# TiltyDuo.net
KiCad netlist of a schematic drawn in EAGLE
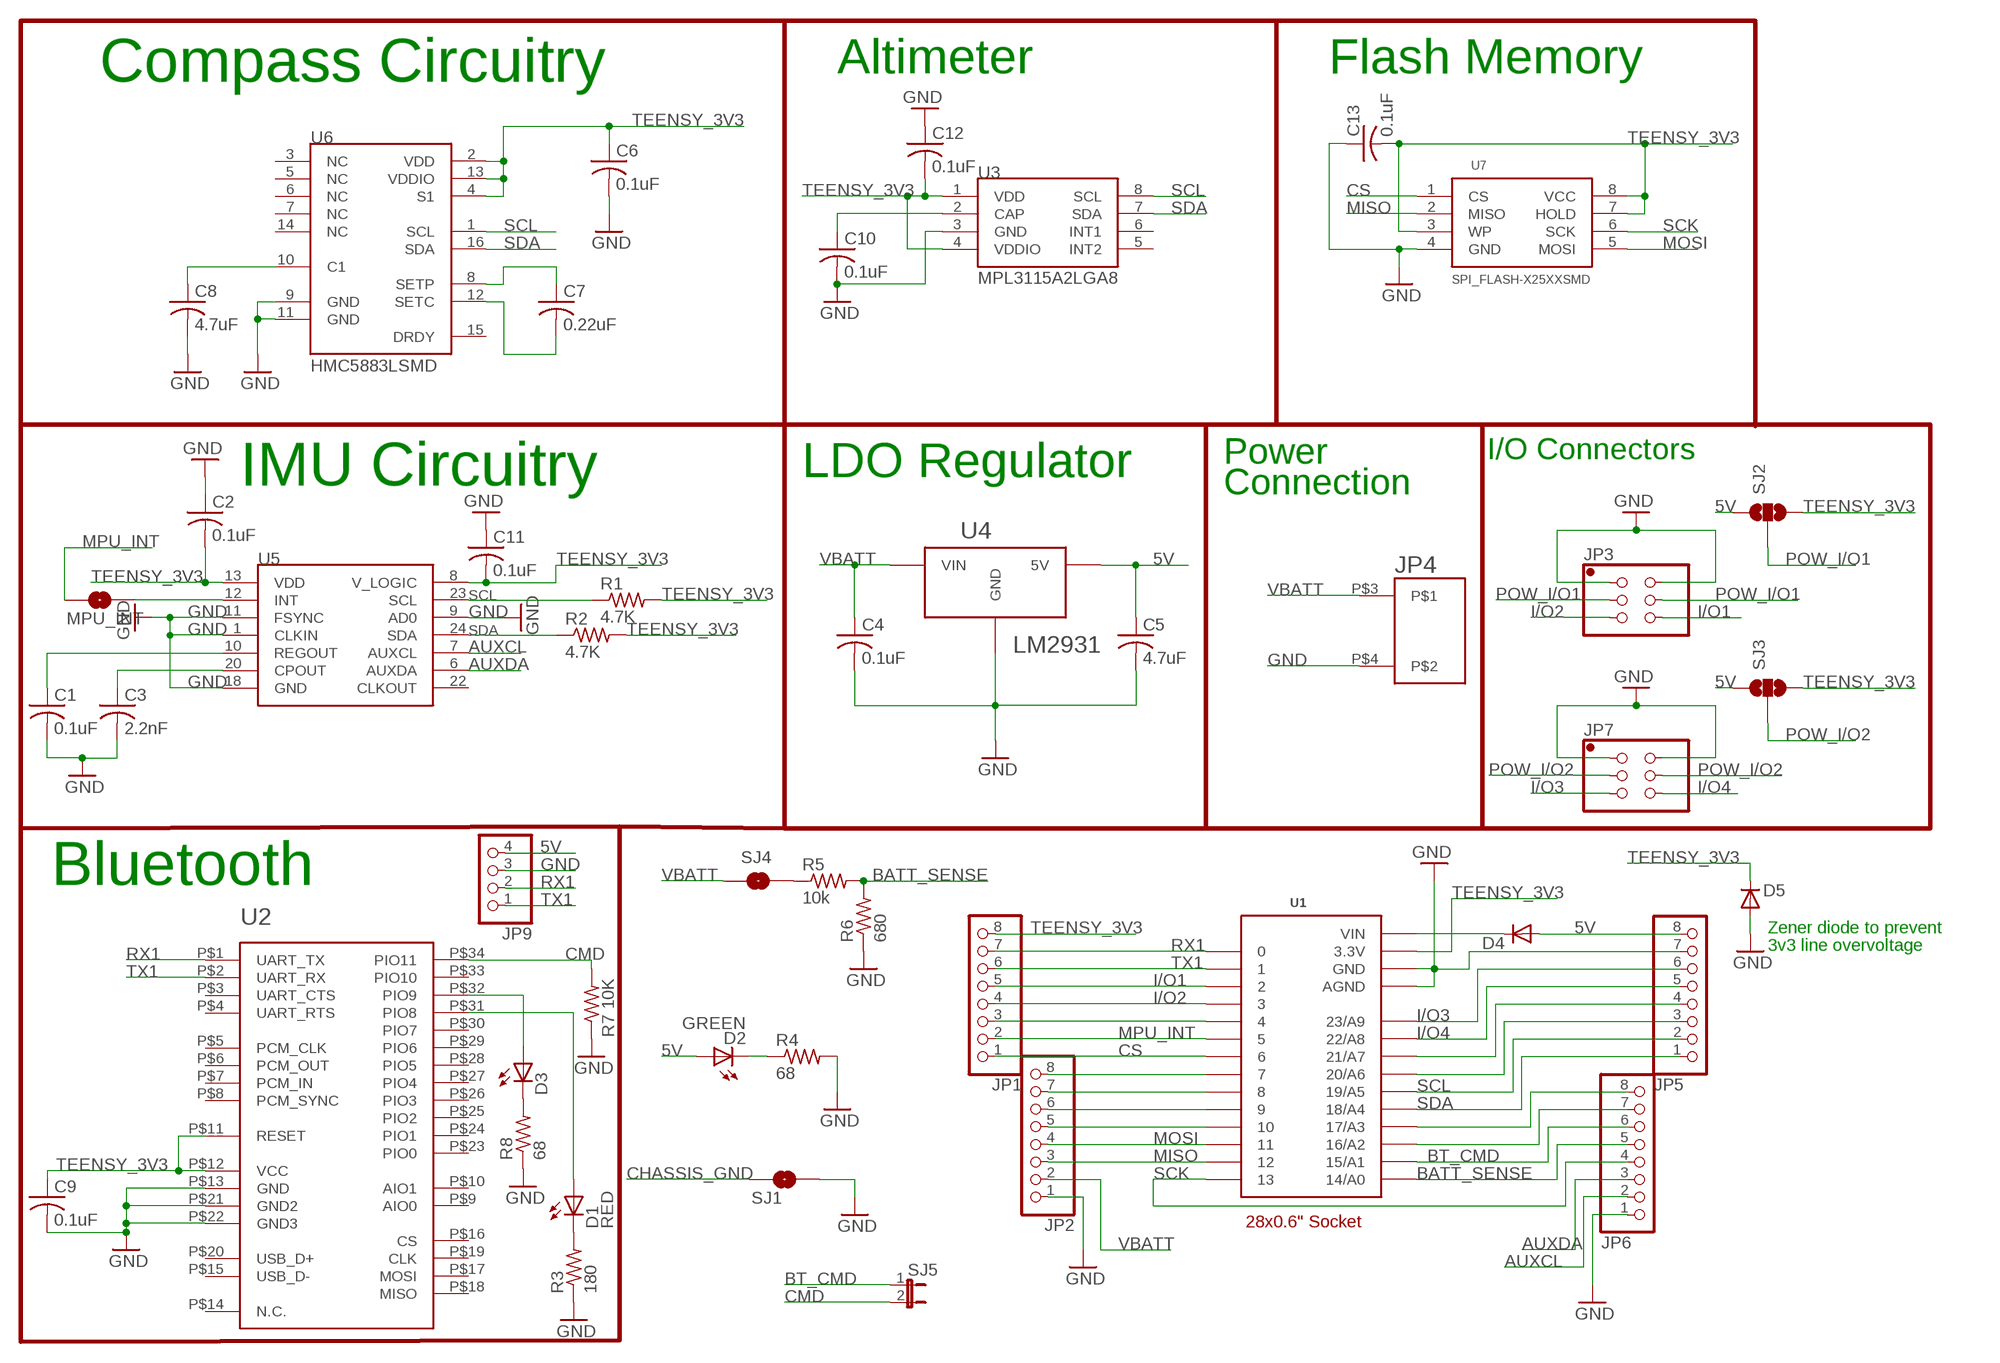
[diagram p0: schematic, sheet 1]

(export (version "E")
  (design (tool "Eeschema 10.0.6"))
  (components
    (comp (ref "C1")
      (value "0.1uF")
      (footprint "eagle-import:C0603")
      (libsource (lib "eagle-import") (part "C-USC0603"))
    )
    (comp (ref "C2")
      (value "0.1uF")
      (footprint "eagle-import:C0603")
      (libsource (lib "eagle-import") (part "C-USC0603"))
    )
    (comp (ref "C3")
      (value "2.2nF")
      (footprint "eagle-import:C0603")
      (libsource (lib "eagle-import") (part "C-USC0603"))
    )
    (comp (ref "C4")
      (value "0.1uF")
      (footprint "eagle-import:C0603")
      (libsource (lib "eagle-import") (part "C-USC0603"))
    )
    (comp (ref "C5")
      (value "4.7uF")
      (footprint "eagle-import:C0603")
      (libsource (lib "eagle-import") (part "C-USC0603"))
    )
    (comp (ref "C6")
      (value "0.1uF")
      (footprint "eagle-import:C0603")
      (libsource (lib "eagle-import") (part "C-USC0603"))
    )
    (comp (ref "C7")
      (value "0.22uF")
      (footprint "eagle-import:C0603")
      (libsource (lib "eagle-import") (part "C-USC0603"))
    )
    (comp (ref "C8")
      (value "4.7uF")
      (footprint "eagle-import:C0603")
      (libsource (lib "eagle-import") (part "C-USC0603"))
    )
    (comp (ref "C9")
      (value "0.1uF")
      (footprint "eagle-import:C0603")
      (libsource (lib "eagle-import") (part "C-USC0603"))
    )
    (comp (ref "C10")
      (value "0.1uF")
      (footprint "eagle-import:C0603")
      (libsource (lib "eagle-import") (part "C-USC0603"))
    )
    (comp (ref "C11")
      (value "0.1uF")
      (footprint "eagle-import:C0603")
      (libsource (lib "eagle-import") (part "C-USC0603"))
    )
    (comp (ref "C12")
      (value "0.1uF")
      (footprint "eagle-import:C0603")
      (libsource (lib "eagle-import") (part "C-USC0603"))
    )
    (comp (ref "C13")
      (value "0.1uF")
      (footprint "eagle-import:C0603")
      (libsource (lib "eagle-import") (part "C-USC0603"))
    )
    (comp (ref "D1")
      (value "RED")
      (footprint "eagle-import:LED-0805")
      (libsource (lib "eagle-import") (part "LED-GREENLED-0805_NO_SILK"))
    )
    (comp (ref "D2")
      (value "GREEN")
      (footprint "eagle-import:LED-0805")
      (libsource (lib "eagle-import") (part "LED-GREENLED-0805_NO_SILK"))
    )
    (comp (ref "D3")
      (value "YELLOW")
      (footprint "eagle-import:LED-0805")
      (libsource (lib "eagle-import") (part "LED-GREENLED-0805_NO_SILK"))
    )
    (comp (ref "D4")
      (value "DIODESOT23")
      (footprint "eagle-import:SOT23-3")
      (fields (field (name "PART#") "BAT54FSTR-ND"))
      (libsource (lib "eagle-import") (part "DIODESOT23"))
    )
    (comp (ref "D5")
      (value "DIODESOT23")
      (footprint "eagle-import:SOT23-3")
      (fields (field (name "PART#") "BZX84C3V3LT1GOSCT-ND"))
      (libsource (lib "eagle-import") (part "DIODESOT23"))
    )
    (comp (ref "JP1")
      (value "PINHD-1X81X08_NO_SILK_LOCK")
      (footprint "eagle-import:1X08_NO_SS_LOCKING")
      (libsource (lib "eagle-import") (part "PINHD-1X81X08_NO_SILK_LOCK"))
    )
    (comp (ref "JP2")
      (value "PINHD-1X81X08_NO_SILK_LOCK")
      (footprint "eagle-import:1X08_NO_SS_LOCKING")
      (libsource (lib "eagle-import") (part "PINHD-1X81X08_NO_SILK_LOCK"))
    )
    (comp (ref "JP3")
      (value "PINHD-2X32X03_NO_SS_LOCK")
      (footprint "eagle-import:2X03_NO_SS_LOCK")
      (libsource (lib "eagle-import") (part "PINHD-2X32X03_NO_SS_LOCK"))
    )
    (comp (ref "JP4")
      (value "2-POS_SMD_TERM_BLOCK")
      (footprint "eagle-import:2-POS_SMD_TERMINAL_BLOCK")
      (fields (field (name "PART#") "277-2337-1-ND"))
      (libsource (lib "eagle-import") (part "2-POS_SMD_TERM_BLOCK"))
    )
    (comp (ref "JP5")
      (value "PINHD-1X81X08_NO_SILK_LOCK")
      (footprint "eagle-import:1X08_NO_SS_LOCKING")
      (libsource (lib "eagle-import") (part "PINHD-1X81X08_NO_SILK_LOCK"))
    )
    (comp (ref "JP6")
      (value "PINHD-1X81X08_NO_SILK_LOCK")
      (footprint "eagle-import:1X08_NO_SS_LOCKING")
      (libsource (lib "eagle-import") (part "PINHD-1X81X08_NO_SILK_LOCK"))
    )
    (comp (ref "JP7")
      (value "PINHD-2X32X03_NO_SS_LOCK")
      (footprint "eagle-import:2X03_NO_SS_LOCK")
      (libsource (lib "eagle-import") (part "PINHD-2X32X03_NO_SS_LOCK"))
    )
    (comp (ref "JP9")
      (value "PINHD-1X41X04_NO_SS_LOCKING")
      (footprint "eagle-import:1X04_NO_SS_LOCKING")
      (libsource (lib "eagle-import") (part "PINHD-1X41X04_NO_SS_LOCKING"))
    )
    (comp (ref "MPU_INT")
      (value "SOLDERJUMPERNO")
      (footprint "eagle-import:SJ_2S-NO")
      (libsource (lib "eagle-import") (part "SOLDERJUMPERNO"))
    )
    (comp (ref "R1")
      (value "4.7K")
      (footprint "eagle-import:R0603")
      (libsource (lib "eagle-import") (part "R-US_R0603"))
    )
    (comp (ref "R2")
      (value "4.7K")
      (footprint "eagle-import:R0603")
      (libsource (lib "eagle-import") (part "R-US_R0603"))
    )
    (comp (ref "R3")
      (value "180")
      (footprint "eagle-import:R0603")
      (libsource (lib "eagle-import") (part "R-US_R0603"))
    )
    (comp (ref "R4")
      (value "68")
      (footprint "eagle-import:R0603")
      (libsource (lib "eagle-import") (part "R-US_R0603"))
    )
    (comp (ref "R5")
      (value "10k")
      (footprint "eagle-import:R0603")
      (libsource (lib "eagle-import") (part "R-US_R0603"))
    )
    (comp (ref "R6")
      (value "680")
      (footprint "eagle-import:R0603")
      (libsource (lib "eagle-import") (part "R-US_R0603"))
    )
    (comp (ref "R7")
      (value "10K")
      (footprint "eagle-import:R0603")
      (libsource (lib "eagle-import") (part "R-US_R0603"))
    )
    (comp (ref "R8")
      (value "68")
      (footprint "eagle-import:R0603")
      (libsource (lib "eagle-import") (part "R-US_R0603"))
    )
    (comp (ref "SJ1")
      (value "SOLDERJUMPERNO")
      (footprint "eagle-import:SJ_2S-NO")
      (libsource (lib "eagle-import") (part "SOLDERJUMPERNO"))
    )
    (comp (ref "SJ2")
      (value "SOLDERJUMPER_2WAYS")
      (footprint "eagle-import:SJ_3")
      (libsource (lib "eagle-import") (part "SOLDERJUMPER_2WAYS"))
    )
    (comp (ref "SJ3")
      (value "SOLDERJUMPER_2WAYS")
      (footprint "eagle-import:SJ_3")
      (libsource (lib "eagle-import") (part "SOLDERJUMPER_2WAYS"))
    )
    (comp (ref "SJ4")
      (value "SOLDERJUMPERTRACE")
      (footprint "eagle-import:SJ_2S-TRACE")
      (libsource (lib "eagle-import") (part "SOLDERJUMPERTRACE"))
    )
    (comp (ref "SJ5")
      (value "JUMPER-2SMD-NC")
      (footprint "eagle-import:SJ_2S")
      (libsource (lib "eagle-import") (part "JUMPER-2SMD-NC"))
    )
    (comp (ref "U1")
      (value "TEENSY_3.0_OUTER-PINS28-DIP_SOCKET")
      (footprint "eagle-import:28-DIP")
      (fields (field (name "PART#") "AE10004-ND"))
      (libsource (lib "eagle-import") (part "TEENSY_3.0_OUTER-PINS28-DIP_SOCKET"))
    )
    (comp (ref "U2")
      (value "HC-09_BREAKOUT")
      (footprint "eagle-import:HC-09_BREAKOUT")
      (libsource (lib "eagle-import") (part "HC-09_BREAKOUT"))
    )
    (comp (ref "U3")
      (value "MPL3115A2LGA8")
      (footprint "eagle-import:LGA8")
      (libsource (lib "eagle-import") (part "MPL3115A2LGA8"))
    )
    (comp (ref "U4")
      (value "LM2931")
      (footprint "eagle-import:TO263")
      (libsource (lib "eagle-import") (part "LM2931"))
    )
    (comp (ref "U5")
      (value "MPU-6050")
      (footprint "eagle-import:QFN-24")
      (libsource (lib "eagle-import") (part "MPU-6050"))
    )
    (comp (ref "U6")
      (value "HMC5883LSMD")
      (footprint "eagle-import:16LPCC")
      (libsource (lib "eagle-import") (part "HMC5883LSMD"))
    )
    (comp (ref "U7")
      (value "SPI_FLASH-X25XXSMD")
      (footprint "eagle-import:SO08")
      (fields (field (name "PART#") "S25FL204K0TMFI043"))
      (libsource (lib "eagle-import") (part "SPI_FLASH-X25XXSMD"))
    )
  )
  (nets
    (net (code "1") (name "/5V") (class "Default")
      (node (ref "C5") (pin "1") (pinfunction "1_1") (pintype "passive"))
      (node (ref "D2") (pin "1") (pinfunction "A_1") (pintype "passive"))
      (node (ref "D4") (pin "1") (pinfunction "A_1") (pintype "passive"))
      (node (ref "JP5") (pin "8") (pinfunction "8_8") (pintype "passive"))
      (node (ref "JP9") (pin "4") (pinfunction "4_4") (pintype "passive"))
      (node (ref "SJ2") (pin "1") (pinfunction "1_1") (pintype "passive"))
      (node (ref "SJ3") (pin "1") (pinfunction "1_1") (pintype "passive"))
      (node (ref "U4") (pin "P$3") (pinfunction "5V_P$3") (pintype "bidirectional"))
    )
    (net (code "2") (name "/AUXCL") (class "Default")
      (node (ref "JP6") (pin "2") (pinfunction "2_2") (pintype "passive"))
      (node (ref "U5") (pin "7") (pinfunction "AUXCL_7") (pintype "bidirectional"))
    )
    (net (code "3") (name "/AUXDA") (class "Default")
      (node (ref "JP6") (pin "3") (pinfunction "3_3") (pintype "passive"))
      (node (ref "U5") (pin "6") (pinfunction "AUXDA_6") (pintype "bidirectional"))
    )
    (net (code "4") (name "/BATT_SENSE") (class "Default")
      (node (ref "JP6") (pin "5") (pinfunction "5_5") (pintype "passive"))
      (node (ref "R5") (pin "2") (pinfunction "2_2") (pintype "passive"))
      (node (ref "R6") (pin "2") (pinfunction "2_2") (pintype "passive"))
      (node (ref "U1") (pin "P$27") (pinfunction "14/A0_P$27") (pintype "bidirectional"))
    )
    (net (code "5") (name "/BT_CMD") (class "Default")
      (node (ref "JP6") (pin "6") (pinfunction "6_6") (pintype "passive"))
      (node (ref "SJ5") (pin "1") (pinfunction "1_1") (pintype "passive"))
      (node (ref "U1") (pin "P$26") (pinfunction "15/A1_P$26") (pintype "bidirectional"))
    )
    (net (code "6") (name "/CHASSIS_GND") (class "Default")
      (node (ref "SJ1") (pin "1") (pinfunction "1_1") (pintype "passive"))
    )
    (net (code "7") (name "/CMD") (class "Default")
      (node (ref "R7") (pin "2") (pinfunction "2_2") (pintype "passive"))
      (node (ref "SJ5") (pin "2") (pinfunction "2_2") (pintype "passive"))
      (node (ref "U2") (pin "P$34") (pinfunction "PIO11_P$34") (pintype "bidirectional"))
    )
    (net (code "8") (name "/CS") (class "Default")
      (node (ref "JP1") (pin "1") (pinfunction "1_1") (pintype "passive"))
      (node (ref "U1") (pin "P$8") (pinfunction "6_P$8") (pintype "bidirectional"))
      (node (ref "U7") (pin "1") (pinfunction "CS_1") (pintype "bidirectional"))
    )
    (net (code "9") (name "/I{slash}O1") (class "Default")
      (node (ref "JP1") (pin "5") (pinfunction "5_5") (pintype "passive"))
      (node (ref "JP3") (pin "6") (pinfunction "6_6") (pintype "passive"))
      (node (ref "U1") (pin "P$4") (pinfunction "2_P$4") (pintype "bidirectional"))
    )
    (net (code "10") (name "/I{slash}O2") (class "Default")
      (node (ref "JP1") (pin "4") (pinfunction "4_4") (pintype "passive"))
      (node (ref "JP3") (pin "5") (pinfunction "5_5") (pintype "passive"))
      (node (ref "U1") (pin "P$5") (pinfunction "3_P$5") (pintype "bidirectional"))
    )
    (net (code "11") (name "/I{slash}O3") (class "Default")
      (node (ref "JP5") (pin "6") (pinfunction "6_6") (pintype "passive"))
      (node (ref "JP7") (pin "5") (pinfunction "5_5") (pintype "passive"))
      (node (ref "U1") (pin "P$18") (pinfunction "23/A9_P$18") (pintype "bidirectional"))
    )
    (net (code "12") (name "/I{slash}O4") (class "Default")
      (node (ref "JP5") (pin "5") (pinfunction "5_5") (pintype "passive"))
      (node (ref "JP7") (pin "6") (pinfunction "6_6") (pintype "passive"))
      (node (ref "U1") (pin "P$19") (pinfunction "22/A8_P$19") (pintype "bidirectional"))
    )
    (net (code "13") (name "/MISO") (class "Default")
      (node (ref "JP2") (pin "3") (pinfunction "3_3") (pintype "passive"))
      (node (ref "U1") (pin "P$14") (pinfunction "12_P$14") (pintype "bidirectional"))
      (node (ref "U7") (pin "2") (pinfunction "MISO_2") (pintype "bidirectional"))
    )
    (net (code "14") (name "/MOSI") (class "Default")
      (node (ref "JP2") (pin "4") (pinfunction "4_4") (pintype "passive"))
      (node (ref "U1") (pin "P$13") (pinfunction "11_P$13") (pintype "bidirectional"))
      (node (ref "U7") (pin "5") (pinfunction "MOSI_5") (pintype "bidirectional"))
    )
    (net (code "15") (name "/MPU_INT") (class "Default")
      (node (ref "JP1") (pin "2") (pinfunction "2_2") (pintype "passive"))
      (node (ref "MPU_INT") (pin "1") (pinfunction "1_1") (pintype "passive"))
      (node (ref "U1") (pin "P$7") (pinfunction "5_P$7") (pintype "bidirectional"))
    )
    (net (code "16") (name "/POW_I{slash}O1") (class "Default")
      (node (ref "JP3") (pin "3") (pinfunction "3_3") (pintype "passive"))
      (node (ref "JP3") (pin "4") (pinfunction "4_4") (pintype "passive"))
      (node (ref "SJ2") (pin "2") (pinfunction "2_2") (pintype "passive"))
    )
    (net (code "17") (name "/POW_I{slash}O2") (class "Default")
      (node (ref "JP7") (pin "3") (pinfunction "3_3") (pintype "passive"))
      (node (ref "JP7") (pin "4") (pinfunction "4_4") (pintype "passive"))
      (node (ref "SJ3") (pin "2") (pinfunction "2_2") (pintype "passive"))
    )
    (net (code "18") (name "/RX1") (class "Default")
      (node (ref "JP1") (pin "7") (pinfunction "7_7") (pintype "passive"))
      (node (ref "JP9") (pin "2") (pinfunction "2_2") (pintype "passive"))
      (node (ref "U1") (pin "P$2") (pinfunction "0_P$2") (pintype "bidirectional"))
      (node (ref "U2") (pin "P$1") (pinfunction "UART_TX_P$1") (pintype "bidirectional"))
    )
    (net (code "19") (name "/SCK") (class "Default")
      (node (ref "JP6") (pin "4") (pinfunction "4_4") (pintype "passive"))
      (node (ref "U1") (pin "P$28") (pinfunction "13_P$28") (pintype "bidirectional"))
      (node (ref "U7") (pin "6") (pinfunction "SCK_6") (pintype "bidirectional"))
    )
    (net (code "20") (name "/SCL") (class "Default")
      (node (ref "JP5") (pin "2") (pinfunction "2_2") (pintype "passive"))
      (node (ref "R1") (pin "1") (pinfunction "1_1") (pintype "passive"))
      (node (ref "U1") (pin "P$22") (pinfunction "19/A5_P$22") (pintype "bidirectional"))
      (node (ref "U3") (pin "8") (pinfunction "SCL_8") (pintype "bidirectional"))
      (node (ref "U5") (pin "23") (pinfunction "SCL_23") (pintype "bidirectional"))
      (node (ref "U6") (pin "1") (pinfunction "SCL_1") (pintype "bidirectional"))
    )
    (net (code "21") (name "/SDA") (class "Default")
      (node (ref "JP5") (pin "1") (pinfunction "1_1") (pintype "passive"))
      (node (ref "R2") (pin "1") (pinfunction "1_1") (pintype "passive"))
      (node (ref "U1") (pin "P$23") (pinfunction "18/A4_P$23") (pintype "bidirectional"))
      (node (ref "U3") (pin "7") (pinfunction "SDA_7") (pintype "bidirectional"))
      (node (ref "U5") (pin "24") (pinfunction "SDA_24") (pintype "bidirectional"))
      (node (ref "U6") (pin "16") (pinfunction "SDA_16") (pintype "bidirectional"))
    )
    (net (code "22") (name "/TEENSY_3V3") (class "Default")
      (node (ref "C11") (pin "2") (pinfunction "2_2") (pintype "passive"))
      (node (ref "C12") (pin "2") (pinfunction "2_2") (pintype "passive"))
      (node (ref "C13") (pin "2") (pinfunction "2_2") (pintype "passive"))
      (node (ref "C2") (pin "2") (pinfunction "2_2") (pintype "passive"))
      (node (ref "C6") (pin "1") (pinfunction "1_1") (pintype "passive"))
      (node (ref "C9") (pin "1") (pinfunction "1_1") (pintype "passive"))
      (node (ref "D5") (pin "3") (pinfunction "C_3") (pintype "passive"))
      (node (ref "JP1") (pin "8") (pinfunction "8_8") (pintype "passive"))
      (node (ref "R1") (pin "2") (pinfunction "2_2") (pintype "passive"))
      (node (ref "R2") (pin "2") (pinfunction "2_2") (pintype "passive"))
      (node (ref "SJ2") (pin "3") (pinfunction "3_3") (pintype "passive"))
      (node (ref "SJ3") (pin "3") (pinfunction "3_3") (pintype "passive"))
      (node (ref "U1") (pin "P$17") (pinfunction "3.3V_P$17") (pintype "power_in"))
      (node (ref "U2") (pin "P$11") (pinfunction "RESET_P$11") (pintype "bidirectional"))
      (node (ref "U2") (pin "P$12") (pinfunction "VCC_P$12") (pintype "bidirectional"))
      (node (ref "U3") (pin "1") (pinfunction "VDD_1") (pintype "bidirectional"))
      (node (ref "U3") (pin "4") (pinfunction "VDDIO_4") (pintype "bidirectional"))
      (node (ref "U5") (pin "13") (pinfunction "VDD_13") (pintype "bidirectional"))
      (node (ref "U5") (pin "8") (pinfunction "V_LOGIC_8") (pintype "bidirectional"))
      (node (ref "U6") (pin "13") (pinfunction "VDDIO_13") (pintype "bidirectional"))
      (node (ref "U6") (pin "2") (pinfunction "VDD_2") (pintype "bidirectional"))
      (node (ref "U6") (pin "4") (pinfunction "S1_4") (pintype "bidirectional"))
      (node (ref "U7") (pin "3") (pinfunction "WP_3") (pintype "bidirectional"))
      (node (ref "U7") (pin "7") (pinfunction "HOLD_7") (pintype "bidirectional"))
      (node (ref "U7") (pin "8") (pinfunction "VCC_8") (pintype "bidirectional"))
    )
    (net (code "23") (name "/TX1") (class "Default")
      (node (ref "JP1") (pin "6") (pinfunction "6_6") (pintype "passive"))
      (node (ref "JP9") (pin "1") (pinfunction "1_1") (pintype "passive"))
      (node (ref "U1") (pin "P$3") (pinfunction "1_P$3") (pintype "bidirectional"))
      (node (ref "U2") (pin "P$2") (pinfunction "UART_RX_P$2") (pintype "bidirectional"))
    )
    (net (code "24") (name "/VBATT") (class "Default")
      (node (ref "C4") (pin "1") (pinfunction "1_1") (pintype "passive"))
      (node (ref "JP2") (pin "2") (pinfunction "2_2") (pintype "passive"))
      (node (ref "JP4") (pin "P$3") (pinfunction "P$1_P$3") (pintype "bidirectional"))
      (node (ref "SJ4") (pin "1") (pinfunction "1_1") (pintype "passive"))
      (node (ref "U4") (pin "P$2") (pinfunction "VIN_P$2") (pintype "bidirectional"))
    )
    (net (code "25") (name "GND") (class "Default")
      (node (ref "C1") (pin "2") (pinfunction "2_2") (pintype "passive"))
      (node (ref "C10") (pin "2") (pinfunction "2_2") (pintype "passive"))
      (node (ref "C11") (pin "1") (pinfunction "1_1") (pintype "passive"))
      (node (ref "C12") (pin "1") (pinfunction "1_1") (pintype "passive"))
      (node (ref "C13") (pin "1") (pinfunction "1_1") (pintype "passive"))
      (node (ref "C2") (pin "1") (pinfunction "1_1") (pintype "passive"))
      (node (ref "C3") (pin "2") (pinfunction "2_2") (pintype "passive"))
      (node (ref "C4") (pin "2") (pinfunction "2_2") (pintype "passive"))
      (node (ref "C5") (pin "2") (pinfunction "2_2") (pintype "passive"))
      (node (ref "C6") (pin "2") (pinfunction "2_2") (pintype "passive"))
      (node (ref "C8") (pin "2") (pinfunction "2_2") (pintype "passive"))
      (node (ref "C9") (pin "2") (pinfunction "2_2") (pintype "passive"))
      (node (ref "D5") (pin "1") (pinfunction "A_1") (pintype "passive"))
      (node (ref "JP2") (pin "1") (pinfunction "1_1") (pintype "passive"))
      (node (ref "JP3") (pin "1") (pinfunction "1_1") (pintype "passive"))
      (node (ref "JP3") (pin "2") (pinfunction "2_2") (pintype "passive"))
      (node (ref "JP4") (pin "P$4") (pinfunction "P$2_P$4") (pintype "bidirectional"))
      (node (ref "JP5") (pin "7") (pinfunction "7_7") (pintype "passive"))
      (node (ref "JP6") (pin "1") (pinfunction "1_1") (pintype "passive"))
      (node (ref "JP7") (pin "1") (pinfunction "1_1") (pintype "passive"))
      (node (ref "JP7") (pin "2") (pinfunction "2_2") (pintype "passive"))
      (node (ref "JP9") (pin "3") (pinfunction "3_3") (pintype "passive"))
      (node (ref "R3") (pin "1") (pinfunction "1_1") (pintype "passive"))
      (node (ref "R4") (pin "2") (pinfunction "2_2") (pintype "passive"))
      (node (ref "R6") (pin "1") (pinfunction "1_1") (pintype "passive"))
      (node (ref "R7") (pin "1") (pinfunction "1_1") (pintype "passive"))
      (node (ref "R8") (pin "1") (pinfunction "1_1") (pintype "passive"))
      (node (ref "SJ1") (pin "2") (pinfunction "2_2") (pintype "passive"))
      (node (ref "U1") (pin "P$1") (pinfunction "GND_P$1") (pintype "power_in"))
      (node (ref "U1") (pin "P$16") (pinfunction "AGND_P$16") (pintype "power_in"))
      (node (ref "U2") (pin "P$13") (pinfunction "GND_P$13") (pintype "bidirectional"))
      (node (ref "U2") (pin "P$21") (pinfunction "GND2_P$21") (pintype "bidirectional"))
      (node (ref "U2") (pin "P$22") (pinfunction "GND3_P$22") (pintype "bidirectional"))
      (node (ref "U3") (pin "3") (pinfunction "GND_3") (pintype "bidirectional"))
      (node (ref "U4") (pin "P$1") (pinfunction "GND_P$1") (pintype "bidirectional"))
      (node (ref "U5") (pin "1") (pinfunction "CLKIN_1") (pintype "bidirectional"))
      (node (ref "U5") (pin "11") (pinfunction "FSYNC_11") (pintype "bidirectional"))
      (node (ref "U5") (pin "18") (pinfunction "GND_18") (pintype "bidirectional"))
      (node (ref "U5") (pin "9") (pinfunction "AD0_9") (pintype "bidirectional"))
      (node (ref "U6") (pin "11") (pinfunction "GND_11") (pintype "bidirectional"))
      (node (ref "U6") (pin "9") (pinfunction "GND_9") (pintype "bidirectional"))
      (node (ref "U7") (pin "4") (pinfunction "GND_4") (pintype "bidirectional"))
    )
    (net (code "26") (name "Net-(D1-A)") (class "Default")
      (node (ref "D1") (pin "1") (pinfunction "A_1") (pintype "passive"))
      (node (ref "U2") (pin "P$31") (pinfunction "PIO8_P$31") (pintype "bidirectional"))
    )
    (net (code "27") (name "Net-(D1-C)") (class "Default")
      (node (ref "D1") (pin "2") (pinfunction "C_2") (pintype "passive"))
      (node (ref "R3") (pin "2") (pinfunction "2_2") (pintype "passive"))
    )
    (net (code "28") (name "Net-(D2-C)") (class "Default")
      (node (ref "D2") (pin "2") (pinfunction "C_2") (pintype "passive"))
      (node (ref "R4") (pin "1") (pinfunction "1_1") (pintype "passive"))
    )
    (net (code "29") (name "Net-(D3-A)") (class "Default")
      (node (ref "D3") (pin "1") (pinfunction "A_1") (pintype "passive"))
      (node (ref "U2") (pin "P$32") (pinfunction "PIO9_P$32") (pintype "bidirectional"))
    )
    (net (code "30") (name "Net-(D3-C)") (class "Default")
      (node (ref "D3") (pin "2") (pinfunction "C_2") (pintype "passive"))
      (node (ref "R8") (pin "2") (pinfunction "2_2") (pintype "passive"))
    )
    (net (code "31") (name "Net-(D4-C)") (class "Default")
      (node (ref "D4") (pin "3") (pinfunction "C_3") (pintype "passive"))
      (node (ref "U1") (pin "P$15") (pinfunction "VIN_P$15") (pintype "power_in"))
    )
    (net (code "32") (name "Net-(R5-Pad1)") (class "Default")
      (node (ref "R5") (pin "1") (pinfunction "1_1") (pintype "passive"))
      (node (ref "SJ4") (pin "2") (pinfunction "2_2") (pintype "passive"))
    )
    (net (code "33") (name "Net-(U1-4)") (class "Default")
      (node (ref "JP1") (pin "3") (pinfunction "3_3") (pintype "passive"))
      (node (ref "U1") (pin "P$6") (pinfunction "4_P$6") (pintype "bidirectional"))
    )
    (net (code "34") (name "Net-(U1-7)") (class "Default")
      (node (ref "JP2") (pin "8") (pinfunction "8_8") (pintype "passive"))
      (node (ref "U1") (pin "P$9") (pinfunction "7_P$9") (pintype "bidirectional"))
    )
    (net (code "35") (name "Net-(U1-8)") (class "Default")
      (node (ref "JP2") (pin "7") (pinfunction "7_7") (pintype "passive"))
      (node (ref "U1") (pin "P$10") (pinfunction "8_P$10") (pintype "bidirectional"))
    )
    (net (code "36") (name "Net-(U1-9)") (class "Default")
      (node (ref "JP2") (pin "6") (pinfunction "6_6") (pintype "passive"))
      (node (ref "U1") (pin "P$11") (pinfunction "9_P$11") (pintype "bidirectional"))
    )
    (net (code "37") (name "Net-(U1-10)") (class "Default")
      (node (ref "JP2") (pin "5") (pinfunction "5_5") (pintype "passive"))
      (node (ref "U1") (pin "P$12") (pinfunction "10_P$12") (pintype "bidirectional"))
    )
    (net (code "38") (name "Net-(U1-16{slash}A2)") (class "Default")
      (node (ref "JP6") (pin "7") (pinfunction "7_7") (pintype "passive"))
      (node (ref "U1") (pin "P$25") (pinfunction "16/A2_P$25") (pintype "bidirectional"))
    )
    (net (code "39") (name "Net-(U1-17{slash}A3)") (class "Default")
      (node (ref "JP6") (pin "8") (pinfunction "8_8") (pintype "passive"))
      (node (ref "U1") (pin "P$24") (pinfunction "17/A3_P$24") (pintype "bidirectional"))
    )
    (net (code "40") (name "Net-(U1-20{slash}A6)") (class "Default")
      (node (ref "JP5") (pin "3") (pinfunction "3_3") (pintype "passive"))
      (node (ref "U1") (pin "P$21") (pinfunction "20/A6_P$21") (pintype "bidirectional"))
    )
    (net (code "41") (name "Net-(U1-21{slash}A7)") (class "Default")
      (node (ref "JP5") (pin "4") (pinfunction "4_4") (pintype "passive"))
      (node (ref "U1") (pin "P$20") (pinfunction "21/A7_P$20") (pintype "bidirectional"))
    )
    (net (code "42") (name "Net-(U3-CAP)") (class "Default")
      (node (ref "C10") (pin "1") (pinfunction "1_1") (pintype "passive"))
      (node (ref "U3") (pin "2") (pinfunction "CAP_2") (pintype "bidirectional"))
    )
    (net (code "43") (name "Net-(U5-CPOUT)") (class "Default")
      (node (ref "C3") (pin "1") (pinfunction "1_1") (pintype "passive"))
      (node (ref "U5") (pin "20") (pinfunction "CPOUT_20") (pintype "bidirectional"))
    )
    (net (code "44") (name "Net-(U5-INT)") (class "Default")
      (node (ref "MPU_INT") (pin "2") (pinfunction "2_2") (pintype "passive"))
      (node (ref "U5") (pin "12") (pinfunction "INT_12") (pintype "bidirectional"))
    )
    (net (code "45") (name "Net-(U5-REGOUT)") (class "Default")
      (node (ref "C1") (pin "1") (pinfunction "1_1") (pintype "passive"))
      (node (ref "U5") (pin "10") (pinfunction "REGOUT_10") (pintype "bidirectional"))
    )
    (net (code "46") (name "Net-(U6-C1)") (class "Default")
      (node (ref "C8") (pin "1") (pinfunction "1_1") (pintype "passive"))
      (node (ref "U6") (pin "10") (pinfunction "C1_10") (pintype "bidirectional"))
    )
    (net (code "47") (name "Net-(U6-SETC)") (class "Default")
      (node (ref "C7") (pin "2") (pinfunction "2_2") (pintype "passive"))
      (node (ref "U6") (pin "12") (pinfunction "SETC_12") (pintype "bidirectional"))
    )
    (net (code "48") (name "Net-(U6-SETP)") (class "Default")
      (node (ref "C7") (pin "1") (pinfunction "1_1") (pintype "passive"))
      (node (ref "U6") (pin "8") (pinfunction "SETP_8") (pintype "bidirectional"))
    )
    (net (code "49") (name "unconnected-(U2-AIO0-PadP$9)") (class "Default")
      (node (ref "U2") (pin "P$9") (pinfunction "AIO0_P$9") (pintype "bidirectional"))
    )
    (net (code "50") (name "unconnected-(U2-AIO1-PadP$10)") (class "Default")
      (node (ref "U2") (pin "P$10") (pinfunction "AIO1_P$10") (pintype "bidirectional"))
    )
    (net (code "51") (name "unconnected-(U2-CLK-PadP$19)") (class "Default")
      (node (ref "U2") (pin "P$19") (pinfunction "CLK_P$19") (pintype "bidirectional"))
    )
    (net (code "52") (name "unconnected-(U2-CS-PadP$16)") (class "Default")
      (node (ref "U2") (pin "P$16") (pinfunction "CS_P$16") (pintype "bidirectional"))
    )
    (net (code "53") (name "unconnected-(U2-MISO-PadP$18)") (class "Default")
      (node (ref "U2") (pin "P$18") (pinfunction "MISO_P$18") (pintype "bidirectional"))
    )
    (net (code "54") (name "unconnected-(U2-MOSI-PadP$17)") (class "Default")
      (node (ref "U2") (pin "P$17") (pinfunction "MOSI_P$17") (pintype "bidirectional"))
    )
    (net (code "55") (name "unconnected-(U2-N.C.-PadP$14)") (class "Default")
      (node (ref "U2") (pin "P$14") (pinfunction "N.C._P$14") (pintype "bidirectional"))
    )
    (net (code "56") (name "unconnected-(U2-PCM_CLK-PadP$5)") (class "Default")
      (node (ref "U2") (pin "P$5") (pinfunction "PCM_CLK_P$5") (pintype "bidirectional"))
    )
    (net (code "57") (name "unconnected-(U2-PCM_IN-PadP$7)") (class "Default")
      (node (ref "U2") (pin "P$7") (pinfunction "PCM_IN_P$7") (pintype "bidirectional"))
    )
    (net (code "58") (name "unconnected-(U2-PCM_OUT-PadP$6)") (class "Default")
      (node (ref "U2") (pin "P$6") (pinfunction "PCM_OUT_P$6") (pintype "bidirectional"))
    )
    (net (code "59") (name "unconnected-(U2-PCM_SYNC-PadP$8)") (class "Default")
      (node (ref "U2") (pin "P$8") (pinfunction "PCM_SYNC_P$8") (pintype "bidirectional"))
    )
    (net (code "60") (name "unconnected-(U2-PIO0-PadP$23)") (class "Default")
      (node (ref "U2") (pin "P$23") (pinfunction "PIO0_P$23") (pintype "bidirectional"))
    )
    (net (code "61") (name "unconnected-(U2-PIO1-PadP$24)") (class "Default")
      (node (ref "U2") (pin "P$24") (pinfunction "PIO1_P$24") (pintype "bidirectional"))
    )
    (net (code "62") (name "unconnected-(U2-PIO2-PadP$25)") (class "Default")
      (node (ref "U2") (pin "P$25") (pinfunction "PIO2_P$25") (pintype "bidirectional"))
    )
    (net (code "63") (name "unconnected-(U2-PIO3-PadP$26)") (class "Default")
      (node (ref "U2") (pin "P$26") (pinfunction "PIO3_P$26") (pintype "bidirectional"))
    )
    (net (code "64") (name "unconnected-(U2-PIO4-PadP$27)") (class "Default")
      (node (ref "U2") (pin "P$27") (pinfunction "PIO4_P$27") (pintype "bidirectional"))
    )
    (net (code "65") (name "unconnected-(U2-PIO5-PadP$28)") (class "Default")
      (node (ref "U2") (pin "P$28") (pinfunction "PIO5_P$28") (pintype "bidirectional"))
    )
    (net (code "66") (name "unconnected-(U2-PIO6-PadP$29)") (class "Default")
      (node (ref "U2") (pin "P$29") (pinfunction "PIO6_P$29") (pintype "bidirectional"))
    )
    (net (code "67") (name "unconnected-(U2-PIO7-PadP$30)") (class "Default")
      (node (ref "U2") (pin "P$30") (pinfunction "PIO7_P$30") (pintype "bidirectional"))
    )
    (net (code "68") (name "unconnected-(U2-PIO10-PadP$33)") (class "Default")
      (node (ref "U2") (pin "P$33") (pinfunction "PIO10_P$33") (pintype "bidirectional"))
    )
    (net (code "69") (name "unconnected-(U2-UART_CTS-PadP$3)") (class "Default")
      (node (ref "U2") (pin "P$3") (pinfunction "UART_CTS_P$3") (pintype "bidirectional"))
    )
    (net (code "70") (name "unconnected-(U2-UART_RTS-PadP$4)") (class "Default")
      (node (ref "U2") (pin "P$4") (pinfunction "UART_RTS_P$4") (pintype "bidirectional"))
    )
    (net (code "71") (name "unconnected-(U2-USB_D+-PadP$20)") (class "Default")
      (node (ref "U2") (pin "P$20") (pinfunction "USB_D+_P$20") (pintype "bidirectional"))
    )
    (net (code "72") (name "unconnected-(U2-USB_D--PadP$15)") (class "Default")
      (node (ref "U2") (pin "P$15") (pinfunction "USB_D-_P$15") (pintype "bidirectional"))
    )
    (net (code "73") (name "unconnected-(U3-INT1-Pad6)") (class "Default")
      (node (ref "U3") (pin "6") (pinfunction "INT1_6") (pintype "bidirectional"))
    )
    (net (code "74") (name "unconnected-(U3-INT2-Pad5)") (class "Default")
      (node (ref "U3") (pin "5") (pinfunction "INT2_5") (pintype "bidirectional"))
    )
    (net (code "75") (name "unconnected-(U5-CLKOUT-Pad22)") (class "Default")
      (node (ref "U5") (pin "22") (pinfunction "CLKOUT_22") (pintype "bidirectional"))
    )
    (net (code "76") (name "unconnected-(U6-DRDY-Pad15)") (class "Default")
      (node (ref "U6") (pin "15") (pinfunction "DRDY_15") (pintype "bidirectional"))
    )
    (net (code "77") (name "unconnected-(U6-NC-Pad3)") (class "Default")
      (node (ref "U6") (pin "3") (pinfunction "NC_3") (pintype "bidirectional"))
    )
    (net (code "78") (name "unconnected-(U6-NC-Pad5)") (class "Default")
      (node (ref "U6") (pin "5") (pinfunction "NC_5") (pintype "bidirectional"))
    )
    (net (code "79") (name "unconnected-(U6-NC-Pad6)") (class "Default")
      (node (ref "U6") (pin "6") (pinfunction "NC_6") (pintype "bidirectional"))
    )
    (net (code "80") (name "unconnected-(U6-NC-Pad7)") (class "Default")
      (node (ref "U6") (pin "7") (pinfunction "NC_7") (pintype "bidirectional"))
    )
    (net (code "81") (name "unconnected-(U6-NC-Pad14)") (class "Default")
      (node (ref "U6") (pin "14") (pinfunction "NC_14") (pintype "bidirectional"))
    )
  )
)
